# Isolator_12.net
KiCad netlist of a schematic drawn in EAGLE
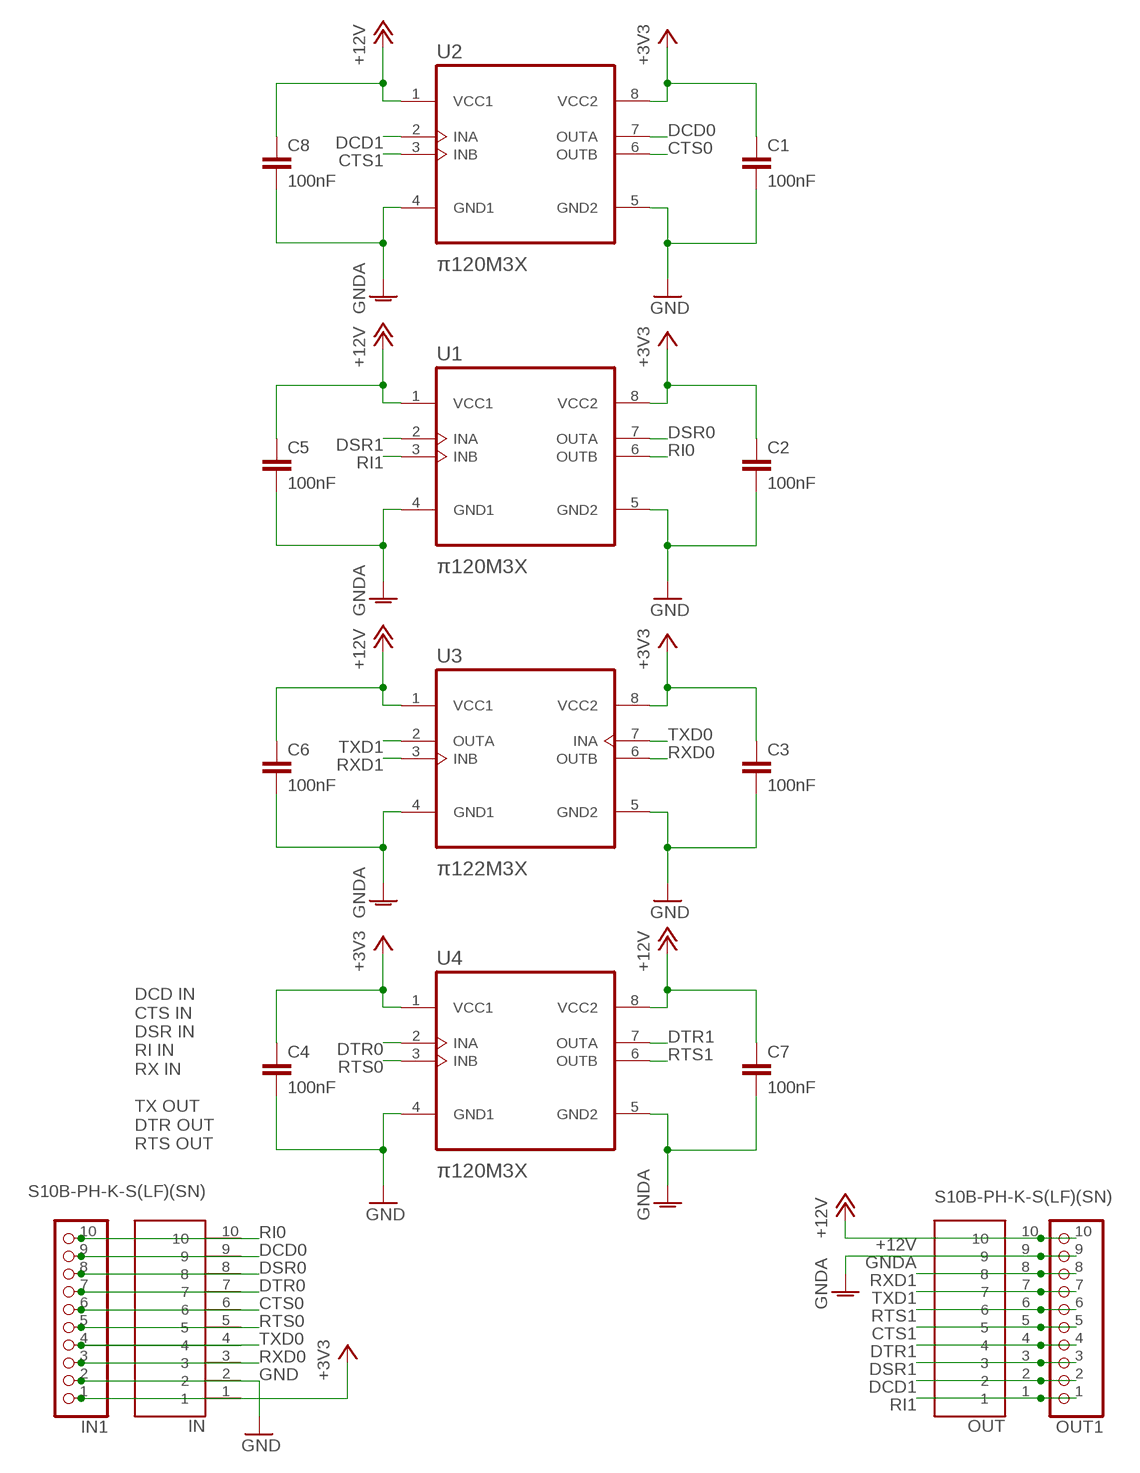
[diagram p0: schematic, sheet 1]

(export (version "E")
  (design (tool "Eeschema 10.0.6"))
  (components
    (comp (ref "C1")
      (value "100nF")
      (footprint "eagle-import:C0805")
      (libsource (lib "eagle-import") (part "C-EUC0805"))
    )
    (comp (ref "C2")
      (value "100nF")
      (footprint "eagle-import:C0805")
      (libsource (lib "eagle-import") (part "C-EUC0805"))
    )
    (comp (ref "C3")
      (value "100nF")
      (footprint "eagle-import:C0805")
      (libsource (lib "eagle-import") (part "C-EUC0805"))
    )
    (comp (ref "C4")
      (value "100nF")
      (footprint "eagle-import:C0805")
      (libsource (lib "eagle-import") (part "C-EUC0805"))
    )
    (comp (ref "C5")
      (value "100nF")
      (footprint "eagle-import:C0805")
      (libsource (lib "eagle-import") (part "C-EUC0805"))
    )
    (comp (ref "C6")
      (value "100nF")
      (footprint "eagle-import:C0805")
      (libsource (lib "eagle-import") (part "C-EUC0805"))
    )
    (comp (ref "C7")
      (value "100nF")
      (footprint "eagle-import:C0805")
      (libsource (lib "eagle-import") (part "C-EUC0805"))
    )
    (comp (ref "C8")
      (value "100nF")
      (footprint "eagle-import:C0805")
      (libsource (lib "eagle-import") (part "C-EUC0805"))
    )
    (comp (ref "IN")
      (value "S10B-PH-K-S(LF)(SN)")
      (footprint "eagle-import:JST_S10B-PH-K-S(LF)(SN)")
      (fields (field (name "MF") "JST Sales") (field (name "MP") "S6B-PH-K-S(LF)(SN)"))
      (libsource (lib "eagle-import") (part "S10B-PH-K-S(LF)(SN)"))
    )
    (comp (ref "IN1")
      (value "PINHD-1X10")
      (footprint "eagle-import:1X10")
      (libsource (lib "eagle-import") (part "PINHD-1X10"))
    )
    (comp (ref "OUT")
      (value "S10B-PH-K-S(LF)(SN)")
      (footprint "eagle-import:JST_S10B-PH-K-S(LF)(SN)")
      (fields (field (name "MF") "JST Sales") (field (name "MP") "S6B-PH-K-S(LF)(SN)"))
      (libsource (lib "eagle-import") (part "S10B-PH-K-S(LF)(SN)"))
    )
    (comp (ref "OUT1")
      (value "PINHD-1X10")
      (footprint "eagle-import:1X10")
      (libsource (lib "eagle-import") (part "PINHD-1X10"))
    )
    (comp (ref "U1")
      (value "π120M3X")
      (footprint "eagle-import:SOIC-8")
      (fields (field (name "MF") "Texas Instruments") (field (name "MP") "ISO7421D"))
      (libsource (lib "eagle-import") (part "π120X3X"))
    )
    (comp (ref "U2")
      (value "π120M3X")
      (footprint "eagle-import:SOIC-8")
      (fields (field (name "MF") "Texas Instruments") (field (name "MP") "ISO7421D"))
      (libsource (lib "eagle-import") (part "π120X3X"))
    )
    (comp (ref "U3")
      (value "π122M3X")
      (footprint "eagle-import:SOIC-8")
      (fields (field (name "MF") "Texas Instruments") (field (name "MP") "ISO7421D"))
      (libsource (lib "eagle-import") (part "π122X3X"))
    )
    (comp (ref "U4")
      (value "π120M3X")
      (footprint "eagle-import:SOIC-8")
      (fields (field (name "MF") "Texas Instruments") (field (name "MP") "ISO7421D"))
      (libsource (lib "eagle-import") (part "π120X3X"))
    )
  )
  (nets
    (net (code "1") (name "+3V3") (class "Default")
      (node (ref "C1") (pin "1") (pinfunction "1_1") (pintype "passive"))
      (node (ref "C2") (pin "1") (pinfunction "1_1") (pintype "passive"))
      (node (ref "C3") (pin "1") (pinfunction "1_1") (pintype "passive"))
      (node (ref "C4") (pin "1") (pinfunction "1_1") (pintype "passive"))
      (node (ref "IN") (pin "1") (pinfunction "1_1") (pintype "passive"))
      (node (ref "IN1") (pin "1") (pinfunction "1_1") (pintype "passive"))
      (node (ref "U1") (pin "8") (pinfunction "VCC2_8") (pintype "power_in"))
      (node (ref "U2") (pin "8") (pinfunction "VCC2_8") (pintype "power_in"))
      (node (ref "U3") (pin "8") (pinfunction "VCC2_8") (pintype "power_in"))
      (node (ref "U4") (pin "1") (pinfunction "VCC1_1") (pintype "power_in"))
    )
    (net (code "2") (name "+12V") (class "Default")
      (node (ref "C5") (pin "1") (pinfunction "1_1") (pintype "passive"))
      (node (ref "C6") (pin "1") (pinfunction "1_1") (pintype "passive"))
      (node (ref "C7") (pin "1") (pinfunction "1_1") (pintype "passive"))
      (node (ref "C8") (pin "1") (pinfunction "1_1") (pintype "passive"))
      (node (ref "OUT") (pin "10") (pinfunction "10_10") (pintype "passive"))
      (node (ref "OUT1") (pin "10") (pinfunction "10_10") (pintype "passive"))
      (node (ref "U1") (pin "1") (pinfunction "VCC1_1") (pintype "power_in"))
      (node (ref "U2") (pin "1") (pinfunction "VCC1_1") (pintype "power_in"))
      (node (ref "U3") (pin "1") (pinfunction "VCC1_1") (pintype "power_in"))
      (node (ref "U4") (pin "8") (pinfunction "VCC2_8") (pintype "power_in"))
    )
    (net (code "3") (name "/CTS0") (class "Default")
      (node (ref "IN") (pin "6") (pinfunction "6_6") (pintype "passive"))
      (node (ref "IN1") (pin "6") (pinfunction "6_6") (pintype "passive"))
      (node (ref "U2") (pin "6") (pinfunction "OUTB_6") (pintype "output"))
    )
    (net (code "4") (name "/CTS1") (class "Default")
      (node (ref "OUT") (pin "5") (pinfunction "5_5") (pintype "passive"))
      (node (ref "OUT1") (pin "5") (pinfunction "5_5") (pintype "passive"))
      (node (ref "U2") (pin "3") (pinfunction "INB_3") (pintype "input"))
    )
    (net (code "5") (name "/DCD0") (class "Default")
      (node (ref "IN") (pin "9") (pinfunction "9_9") (pintype "passive"))
      (node (ref "IN1") (pin "9") (pinfunction "9_9") (pintype "passive"))
      (node (ref "U2") (pin "7") (pinfunction "OUTA_7") (pintype "output"))
    )
    (net (code "6") (name "/DCD1") (class "Default")
      (node (ref "OUT") (pin "2") (pinfunction "2_2") (pintype "passive"))
      (node (ref "OUT1") (pin "2") (pinfunction "2_2") (pintype "passive"))
      (node (ref "U2") (pin "2") (pinfunction "INA_2") (pintype "input"))
    )
    (net (code "7") (name "/DSR0") (class "Default")
      (node (ref "IN") (pin "8") (pinfunction "8_8") (pintype "passive"))
      (node (ref "IN1") (pin "8") (pinfunction "8_8") (pintype "passive"))
      (node (ref "U1") (pin "7") (pinfunction "OUTA_7") (pintype "output"))
    )
    (net (code "8") (name "/DSR1") (class "Default")
      (node (ref "OUT") (pin "3") (pinfunction "3_3") (pintype "passive"))
      (node (ref "OUT1") (pin "3") (pinfunction "3_3") (pintype "passive"))
      (node (ref "U1") (pin "2") (pinfunction "INA_2") (pintype "input"))
    )
    (net (code "9") (name "/DTR0") (class "Default")
      (node (ref "IN") (pin "7") (pinfunction "7_7") (pintype "passive"))
      (node (ref "IN1") (pin "7") (pinfunction "7_7") (pintype "passive"))
      (node (ref "U4") (pin "2") (pinfunction "INA_2") (pintype "input"))
    )
    (net (code "10") (name "/DTR1") (class "Default")
      (node (ref "OUT") (pin "4") (pinfunction "4_4") (pintype "passive"))
      (node (ref "OUT1") (pin "4") (pinfunction "4_4") (pintype "passive"))
      (node (ref "U4") (pin "7") (pinfunction "OUTA_7") (pintype "output"))
    )
    (net (code "11") (name "/RI0") (class "Default")
      (node (ref "IN") (pin "10") (pinfunction "10_10") (pintype "passive"))
      (node (ref "IN1") (pin "10") (pinfunction "10_10") (pintype "passive"))
      (node (ref "U1") (pin "6") (pinfunction "OUTB_6") (pintype "output"))
    )
    (net (code "12") (name "/RI1") (class "Default")
      (node (ref "OUT") (pin "1") (pinfunction "1_1") (pintype "passive"))
      (node (ref "OUT1") (pin "1") (pinfunction "1_1") (pintype "passive"))
      (node (ref "U1") (pin "3") (pinfunction "INB_3") (pintype "input"))
    )
    (net (code "13") (name "/RTS0") (class "Default")
      (node (ref "IN") (pin "5") (pinfunction "5_5") (pintype "passive"))
      (node (ref "IN1") (pin "5") (pinfunction "5_5") (pintype "passive"))
      (node (ref "U4") (pin "3") (pinfunction "INB_3") (pintype "input"))
    )
    (net (code "14") (name "/RTS1") (class "Default")
      (node (ref "OUT") (pin "6") (pinfunction "6_6") (pintype "passive"))
      (node (ref "OUT1") (pin "6") (pinfunction "6_6") (pintype "passive"))
      (node (ref "U4") (pin "6") (pinfunction "OUTB_6") (pintype "output"))
    )
    (net (code "15") (name "/RXD0") (class "Default")
      (node (ref "IN") (pin "3") (pinfunction "3_3") (pintype "passive"))
      (node (ref "IN1") (pin "3") (pinfunction "3_3") (pintype "passive"))
      (node (ref "U3") (pin "6") (pinfunction "OUTB_6") (pintype "output"))
    )
    (net (code "16") (name "/RXD1") (class "Default")
      (node (ref "OUT") (pin "8") (pinfunction "8_8") (pintype "passive"))
      (node (ref "OUT1") (pin "8") (pinfunction "8_8") (pintype "passive"))
      (node (ref "U3") (pin "3") (pinfunction "INB_3") (pintype "input"))
    )
    (net (code "17") (name "/TXD0") (class "Default")
      (node (ref "IN") (pin "4") (pinfunction "4_4") (pintype "passive"))
      (node (ref "IN1") (pin "4") (pinfunction "4_4") (pintype "passive"))
      (node (ref "U3") (pin "7") (pinfunction "INA_7") (pintype "input"))
    )
    (net (code "18") (name "/TXD1") (class "Default")
      (node (ref "OUT") (pin "7") (pinfunction "7_7") (pintype "passive"))
      (node (ref "OUT1") (pin "7") (pinfunction "7_7") (pintype "passive"))
      (node (ref "U3") (pin "2") (pinfunction "OUTA_2") (pintype "output"))
    )
    (net (code "19") (name "GND") (class "Default")
      (node (ref "C1") (pin "2") (pinfunction "2_2") (pintype "passive"))
      (node (ref "C2") (pin "2") (pinfunction "2_2") (pintype "passive"))
      (node (ref "C3") (pin "2") (pinfunction "2_2") (pintype "passive"))
      (node (ref "C4") (pin "2") (pinfunction "2_2") (pintype "passive"))
      (node (ref "IN") (pin "2") (pinfunction "2_2") (pintype "passive"))
      (node (ref "IN1") (pin "2") (pinfunction "2_2") (pintype "passive"))
      (node (ref "U1") (pin "5") (pinfunction "GND2_5") (pintype "power_in"))
      (node (ref "U2") (pin "5") (pinfunction "GND2_5") (pintype "power_in"))
      (node (ref "U3") (pin "5") (pinfunction "GND2_5") (pintype "power_in"))
      (node (ref "U4") (pin "4") (pinfunction "GND1_4") (pintype "power_in"))
    )
    (net (code "20") (name "GNDA") (class "Default")
      (node (ref "C5") (pin "2") (pinfunction "2_2") (pintype "passive"))
      (node (ref "C6") (pin "2") (pinfunction "2_2") (pintype "passive"))
      (node (ref "C7") (pin "2") (pinfunction "2_2") (pintype "passive"))
      (node (ref "C8") (pin "2") (pinfunction "2_2") (pintype "passive"))
      (node (ref "OUT") (pin "9") (pinfunction "9_9") (pintype "passive"))
      (node (ref "OUT1") (pin "9") (pinfunction "9_9") (pintype "passive"))
      (node (ref "U1") (pin "4") (pinfunction "GND1_4") (pintype "power_in"))
      (node (ref "U2") (pin "4") (pinfunction "GND1_4") (pintype "power_in"))
      (node (ref "U3") (pin "4") (pinfunction "GND1_4") (pintype "power_in"))
      (node (ref "U4") (pin "5") (pinfunction "GND2_5") (pintype "power_in"))
    )
  )
)
